# ProProject_HV_No_Display_2024-06-09.net
KiCad netlist of a schematic drawn in EasyEDA Pro
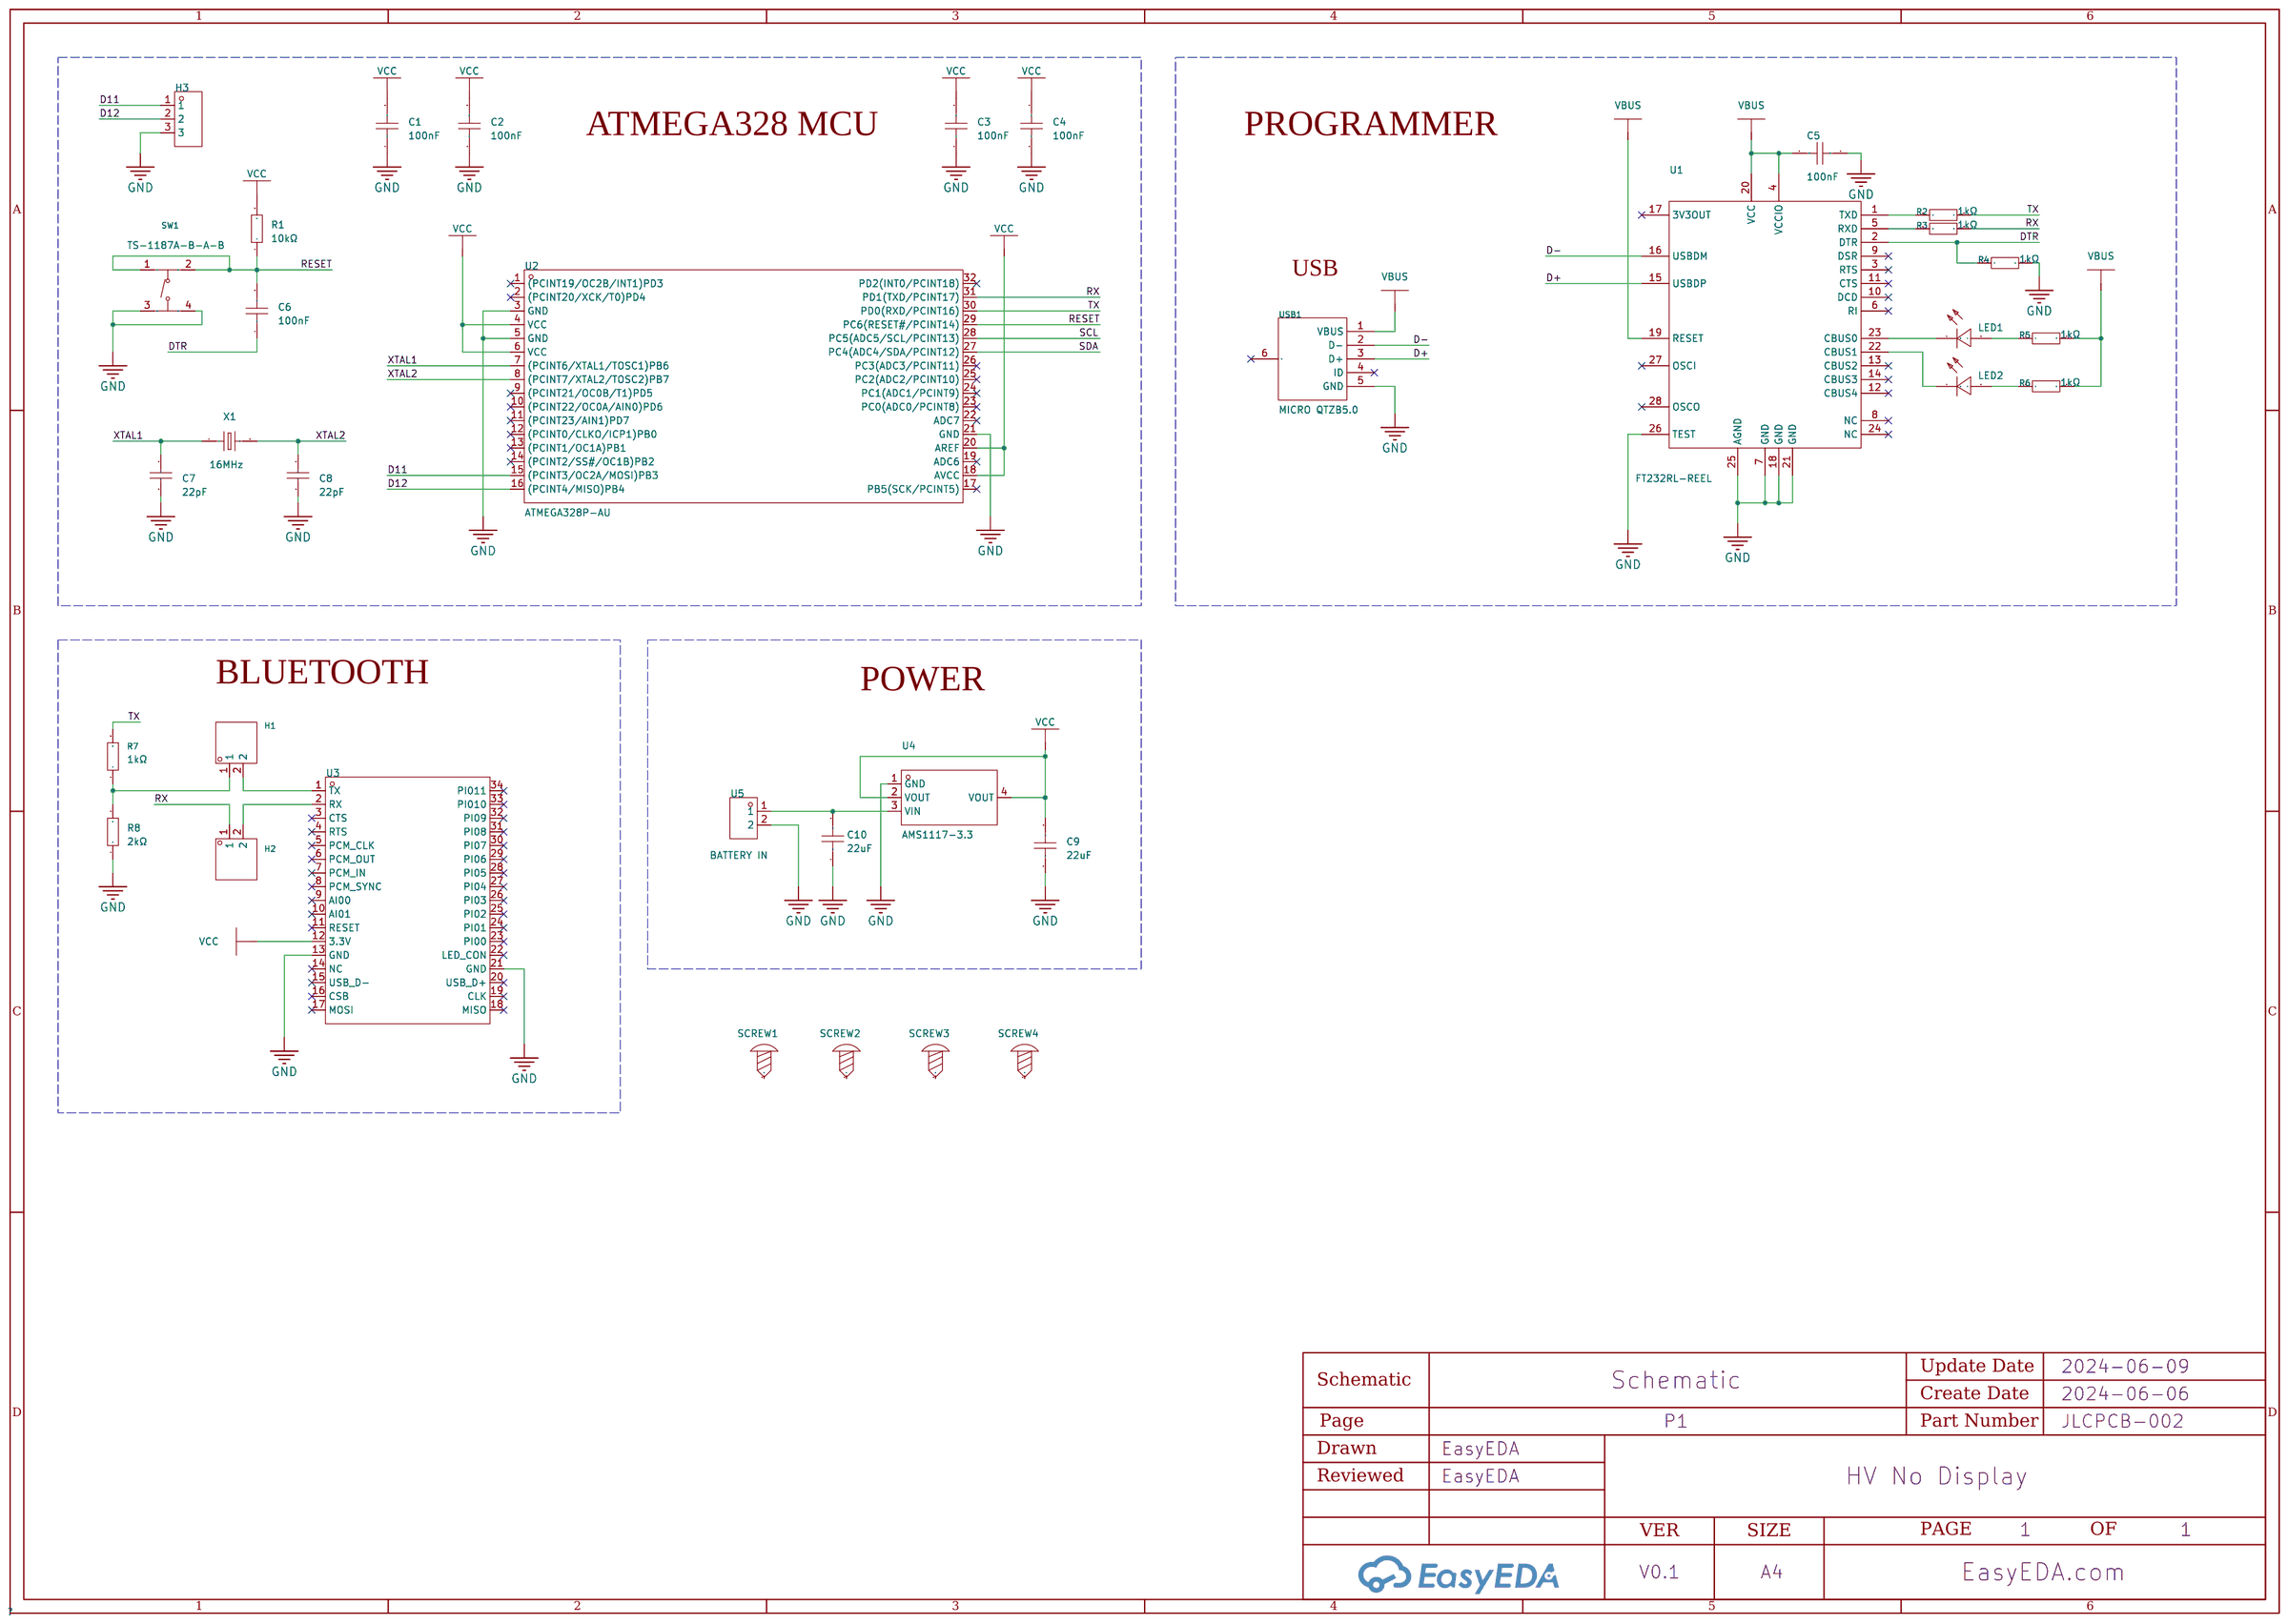
[diagram p0: schematic sheet]

(export (version "E")
  (design (tool "Eeschema 10.0.6"))
  (components
    (comp (ref "C1")
      (value "100nF")
      (footprint "easyedapro:C0402")
      (fields
        (field (name "Manufacturer Part") "CL05B104KB54PNC")
        (field (name "Manufacturer") "SAMSUNG(三星)")
      )
      (libsource (lib "easyedapro") (part "CL05B104KB54PNC"))
    )
    (comp (ref "C2")
      (value "100nF")
      (footprint "easyedapro:C0402")
      (fields
        (field (name "Manufacturer Part") "CL05B104KB54PNC")
        (field (name "Manufacturer") "SAMSUNG(三星)")
      )
      (libsource (lib "easyedapro") (part "CL05B104KB54PNC"))
    )
    (comp (ref "C3")
      (value "100nF")
      (footprint "easyedapro:C0402")
      (fields
        (field (name "Manufacturer Part") "CL05B104KB54PNC")
        (field (name "Manufacturer") "SAMSUNG(三星)")
      )
      (libsource (lib "easyedapro") (part "CL05B104KB54PNC"))
    )
    (comp (ref "C4")
      (value "100nF")
      (footprint "easyedapro:C0402")
      (fields
        (field (name "Manufacturer Part") "CL05B104KB54PNC")
        (field (name "Manufacturer") "SAMSUNG(三星)")
      )
      (libsource (lib "easyedapro") (part "CL05B104KB54PNC"))
    )
    (comp (ref "C5")
      (value "100nF")
      (footprint "easyedapro:C0402")
      (fields
        (field (name "Manufacturer Part") "CL05B104KB54PNC")
        (field (name "Manufacturer") "SAMSUNG(三星)")
      )
      (libsource (lib "easyedapro") (part "CL05B104KB54PNC"))
    )
    (comp (ref "C6")
      (value "100nF")
      (footprint "easyedapro:C0402")
      (fields
        (field (name "Manufacturer Part") "CL05B104KB54PNC")
        (field (name "Manufacturer") "SAMSUNG(三星)")
      )
      (libsource (lib "easyedapro") (part "CL05B104KB54PNC"))
    )
    (comp (ref "C7")
      (value "22pF")
      (footprint "easyedapro:C0402")
      (fields (field (name "Manufacturer Part") "0402CG220J500NT") (field (name "Manufacturer") "FH(风华)"))
      (libsource (lib "easyedapro") (part "0402CG220J500NT"))
    )
    (comp (ref "C8")
      (value "22pF")
      (footprint "easyedapro:C0402")
      (fields (field (name "Manufacturer Part") "0402CG220J500NT") (field (name "Manufacturer") "FH(风华)"))
      (libsource (lib "easyedapro") (part "0402CG220J500NT"))
    )
    (comp (ref "C9")
      (value "22uF")
      (footprint "easyedapro:C0805")
      (fields
        (field (name "Manufacturer Part") "CL21A226MAQNNNE")
        (field (name "Manufacturer") "SAMSUNG(三星)")
      )
      (libsource (lib "easyedapro") (part "CL21A226MAQNNNE"))
    )
    (comp (ref "C10")
      (value "22uF")
      (footprint "easyedapro:C0805")
      (fields
        (field (name "Manufacturer Part") "CL21A226MAQNNNE")
        (field (name "Manufacturer") "SAMSUNG(三星)")
      )
      (libsource (lib "easyedapro") (part "CL21A226MAQNNNE"))
    )
    (comp (ref "H1")
      (value "~")
      (footprint "easyedapro:HDR-TH_2P-P2.54-V-M-1")
      (libsource (lib "easyedapro") (part "210S-1*2P L=11.6MMGold-plated black"))
    )
    (comp (ref "H2")
      (value "~")
      (footprint "easyedapro:HDR-TH_2P-P2.54-V-M-1")
      (libsource (lib "easyedapro") (part "210S-1*2P L=11.6MMGold-plated black"))
    )
    (comp (ref "H3")
      (value "~")
      (footprint "easyedapro:HDR-TH_3P-P2.54-V-M")
      (libsource (lib "easyedapro") (part "PZ254V-11-03P_C2937625"))
    )
    (comp (ref "LED1")
      (value "TJ-S1005SW4TGLC2R-A5")
      (footprint "easyedapro:LED0402-RD")
      (description "Emitted Color:Red")
      (fields (field (name "Manufacturer") "TOGIALED(统佳)"))
      (libsource (lib "easyedapro") (part "TJ-S1005SW4TGLC2R-A5"))
    )
    (comp (ref "LED2")
      (value "TJ-S1005SW4TGLC2R-A5")
      (footprint "easyedapro:LED0402-RD")
      (description "Emitted Color:Red")
      (fields (field (name "Manufacturer") "TOGIALED(统佳)"))
      (libsource (lib "easyedapro") (part "TJ-S1005SW4TGLC2R-A5"))
    )
    (comp (ref "R1")
      (value "10kΩ")
      (footprint "easyedapro:R0402")
      (fields
        (field (name "Manufacturer Part") "0402WGF1002TCE")
        (field (name "Manufacturer") "UNI-ROYAL(厚声)")
      )
      (libsource (lib "easyedapro") (part "0402WGF1002TCE"))
    )
    (comp (ref "R2")
      (value "1kΩ")
      (footprint "easyedapro:R0402")
      (fields
        (field (name "Manufacturer Part") "0402WGF1001TCE")
        (field (name "Manufacturer") "UNI-ROYAL(厚声)")
      )
      (libsource (lib "easyedapro") (part "0402WGF1001TCE"))
    )
    (comp (ref "R3")
      (value "1kΩ")
      (footprint "easyedapro:R0402")
      (fields
        (field (name "Manufacturer Part") "0402WGF1001TCE")
        (field (name "Manufacturer") "UNI-ROYAL(厚声)")
      )
      (libsource (lib "easyedapro") (part "0402WGF1001TCE"))
    )
    (comp (ref "R4")
      (value "1kΩ")
      (footprint "easyedapro:R0402")
      (fields
        (field (name "Manufacturer Part") "0402WGF1001TCE")
        (field (name "Manufacturer") "UNI-ROYAL(厚声)")
      )
      (libsource (lib "easyedapro") (part "0402WGF1001TCE"))
    )
    (comp (ref "R5")
      (value "1kΩ")
      (footprint "easyedapro:R0402")
      (fields
        (field (name "Manufacturer Part") "0402WGF1001TCE")
        (field (name "Manufacturer") "UNI-ROYAL(厚声)")
      )
      (libsource (lib "easyedapro") (part "0402WGF1001TCE"))
    )
    (comp (ref "R6")
      (value "1kΩ")
      (footprint "easyedapro:R0402")
      (fields
        (field (name "Manufacturer Part") "0402WGF1001TCE")
        (field (name "Manufacturer") "UNI-ROYAL(厚声)")
      )
      (libsource (lib "easyedapro") (part "0402WGF1001TCE"))
    )
    (comp (ref "R7")
      (value "1kΩ")
      (footprint "easyedapro:R0402")
      (fields
        (field (name "Manufacturer Part") "0402WGF1001TCE")
        (field (name "Manufacturer") "UNI-ROYAL(厚声)")
      )
      (libsource (lib "easyedapro") (part "0402WGF1001TCE"))
    )
    (comp (ref "R8")
      (value "2kΩ")
      (footprint "easyedapro:R0402")
      (fields
        (field (name "Manufacturer Part") "0402WGF2001TCE")
        (field (name "Manufacturer") "UNI-ROYAL(厚声)")
      )
      (libsource (lib "easyedapro") (part "0402WGF2001TCE"))
    )
    (comp (ref "SCREW1")
      (value "~")
      (footprint "easyedapro:Screw-Hole-M2")
      (libsource (lib "easyedapro") (part "Screw-Hole"))
    )
    (comp (ref "SCREW2")
      (value "~")
      (footprint "easyedapro:Screw-Hole-M2")
      (libsource (lib "easyedapro") (part "Screw-Hole"))
    )
    (comp (ref "SCREW3")
      (value "~")
      (footprint "easyedapro:Screw-Hole-M2")
      (libsource (lib "easyedapro") (part "Screw-Hole"))
    )
    (comp (ref "SCREW4")
      (value "~")
      (footprint "easyedapro:Screw-Hole-M2")
      (libsource (lib "easyedapro") (part "Screw-Hole"))
    )
    (comp (ref "SW1")
      (value "TS-1187A-B-A-B")
      (footprint "easyedapro:SW-SMD_4P-L5.1-W5.1-P3.70-LS6.5-TL-2")
      (fields (field (name "Manufacturer") "XKB Connectivity(中国星坤)"))
      (libsource (lib "easyedapro") (part "TS-1187A-B-A-B"))
    )
    (comp (ref "U1")
      (value "FT232RL-REEL")
      (footprint "easyedapro:SSOP-28_L10.2-W5.3-P0.65-LS7.8-BL")
      (fields (field (name "Manufacturer") "FTDI(飞特帝亚)"))
      (libsource (lib "easyedapro") (part "FT232RL-REEL"))
    )
    (comp (ref "U2")
      (value "ATMEGA328P-AU")
      (footprint "easyedapro:TQFP-32_L7.0-W7.0-P0.80-LS9.0-BL")
      (fields (field (name "Manufacturer") "MICROCHIP(美国微芯)"))
      (libsource (lib "easyedapro") (part "ATMEGA328P-AU"))
    )
    (comp (ref "U3")
      (value "{ManufacturerPart!}")
      (footprint "easyedapro:BULETM-SMD_HC-05")
      (fields (field (name "Manufacturer Part") "HC-05"))
      (libsource (lib "easyedapro") (part "HC-05"))
    )
    (comp (ref "U4")
      (value "AMS1117-3.3")
      (footprint "easyedapro:SOT-223-3_L6.5-W3.4-P2.30-LS7.0-BR")
      (fields (field (name "Manufacturer") "AMS"))
      (libsource (lib "easyedapro") (part "AMS1117-3.3"))
    )
    (comp (ref "U5")
      (value "BATTERY IN")
      (footprint "easyedapro:CONN-TH_2P-P5.08_DB128L-5.08-2P")
      (fields (field (name "Manufacturer") "DORABO(地博电气)"))
      (libsource (lib "easyedapro") (part "DB128L-5.08-2P"))
    )
    (comp (ref "USB1")
      (value "MICRO QTZB5.0")
      (footprint "easyedapro:MICRO-USB-SMD_MICRO-QTZB5.0")
      (fields (field (name "Manufacturer") "SHOU HAN(首韩)"))
      (libsource (lib "easyedapro") (part "MICRO QTZB5.0"))
    )
    (comp (ref "X1")
      (value "16MHz")
      (footprint "easyedapro:HC-49S_L11.4-W4.8")
      (fields (field (name "Manufacturer Part") "TAXM16M2GLFBET2T") (field (name "Manufacturer") "YJX(雅晶鑫)"))
      (libsource (lib "easyedapro") (part "HC-49SM16MHz20pF30ppm"))
    )
  )
  (nets
    (net (code "1") (name "/D+") (class "Default")
      (node (ref "U1") (pin "15") (pinfunction "USBDP_15") (pintype "bidirectional"))
      (node (ref "USB1") (pin "3") (pinfunction "D+_3") (pintype "input"))
    )
    (net (code "2") (name "/D-") (class "Default")
      (node (ref "U1") (pin "16") (pinfunction "USBDM_16") (pintype "bidirectional"))
      (node (ref "USB1") (pin "2") (pinfunction "D-_2") (pintype "input"))
    )
    (net (code "3") (name "/D11") (class "Default")
      (node (ref "H3") (pin "1") (pinfunction "1_1") (pintype "input"))
      (node (ref "U2") (pin "15") (pinfunction "(PCINT3/OC2A/MOSI)PB3_15") (pintype "unspecified"))
    )
    (net (code "4") (name "/D12") (class "Default")
      (node (ref "H3") (pin "2") (pinfunction "2_2") (pintype "input"))
      (node (ref "U2") (pin "16") (pinfunction "(PCINT4/MISO)PB4_16") (pintype "unspecified"))
    )
    (net (code "5") (name "/DTR") (class "Default")
      (node (ref "C6") (pin "1") (pinfunction "1_1") (pintype "input"))
      (node (ref "R4") (pin "1") (pinfunction "1_1") (pintype "input"))
      (node (ref "U1") (pin "2") (pinfunction "DTR_2") (pintype "output"))
    )
    (net (code "6") (name "/RESET") (class "Default")
      (node (ref "C6") (pin "2") (pinfunction "2_2") (pintype "input"))
      (node (ref "R1") (pin "1") (pinfunction "1_1") (pintype "input"))
      (node (ref "SW1") (pin "1") (pinfunction "A_1") (pintype "input"))
      (node (ref "SW1") (pin "2") (pinfunction "B_2") (pintype "input"))
      (node (ref "U2") (pin "29") (pinfunction "PC6(RESET#/PCINT14)_29") (pintype "unspecified"))
    )
    (net (code "7") (name "/RX") (class "Default")
      (node (ref "H2") (pin "1") (pinfunction "1_1") (pintype "input"))
      (node (ref "R3") (pin "2") (pinfunction "2_2") (pintype "input"))
      (node (ref "U2") (pin "31") (pinfunction "PD1(TXD/PCINT17)_31") (pintype "unspecified"))
    )
    (net (code "8") (name "/SCL") (class "Default")
      (node (ref "U2") (pin "28") (pinfunction "PC5(ADC5/SCL/PCINT13)_28") (pintype "unspecified"))
    )
    (net (code "9") (name "/SDA") (class "Default")
      (node (ref "U2") (pin "27") (pinfunction "PC4(ADC4/SDA/PCINT12)_27") (pintype "unspecified"))
    )
    (net (code "10") (name "/TX") (class "Default")
      (node (ref "R2") (pin "2") (pinfunction "2_2") (pintype "input"))
      (node (ref "R7") (pin "2") (pinfunction "2_2") (pintype "input"))
      (node (ref "U2") (pin "30") (pinfunction "PD0(RXD/PCINT16)_30") (pintype "unspecified"))
    )
    (net (code "11") (name "/XTAL1") (class "Default")
      (node (ref "C7") (pin "2") (pinfunction "2_2") (pintype "input"))
      (node (ref "U2") (pin "7") (pinfunction "(PCINT6/XTAL1/TOSC1)PB6_7") (pintype "unspecified"))
      (node (ref "X1") (pin "1") (pinfunction "1_1") (pintype "unspecified"))
    )
    (net (code "12") (name "/XTAL2") (class "Default")
      (node (ref "C8") (pin "2") (pinfunction "2_2") (pintype "input"))
      (node (ref "U2") (pin "8") (pinfunction "(PCINT7/XTAL2/TOSC2)PB7_8") (pintype "unspecified"))
      (node (ref "X1") (pin "2") (pinfunction "2_2") (pintype "unspecified"))
    )
    (net (code "13") (name "GND") (class "Default")
      (node (ref "C1") (pin "1") (pinfunction "1_1") (pintype "input"))
      (node (ref "C10") (pin "1") (pinfunction "1_1") (pintype "unspecified"))
      (node (ref "C2") (pin "1") (pinfunction "1_1") (pintype "input"))
      (node (ref "C3") (pin "1") (pinfunction "1_1") (pintype "input"))
      (node (ref "C4") (pin "1") (pinfunction "1_1") (pintype "input"))
      (node (ref "C5") (pin "1") (pinfunction "1_1") (pintype "input"))
      (node (ref "C7") (pin "1") (pinfunction "1_1") (pintype "input"))
      (node (ref "C8") (pin "1") (pinfunction "1_1") (pintype "input"))
      (node (ref "C9") (pin "1") (pinfunction "1_1") (pintype "unspecified"))
      (node (ref "H3") (pin "3") (pinfunction "3_3") (pintype "input"))
      (node (ref "R4") (pin "2") (pinfunction "2_2") (pintype "input"))
      (node (ref "R8") (pin "1") (pinfunction "1_1") (pintype "input"))
      (node (ref "SW1") (pin "3") (pinfunction "C_3") (pintype "input"))
      (node (ref "SW1") (pin "4") (pinfunction "D_4") (pintype "input"))
      (node (ref "U1") (pin "18") (pinfunction "GND_18") (pintype "unspecified"))
      (node (ref "U1") (pin "21") (pinfunction "GND_21") (pintype "unspecified"))
      (node (ref "U1") (pin "25") (pinfunction "AGND_25") (pintype "unspecified"))
      (node (ref "U1") (pin "26") (pinfunction "TEST_26") (pintype "unspecified"))
      (node (ref "U1") (pin "7") (pinfunction "GND_7") (pintype "unspecified"))
      (node (ref "U2") (pin "21") (pinfunction "GND_21") (pintype "unspecified"))
      (node (ref "U2") (pin "3") (pinfunction "GND_3") (pintype "unspecified"))
      (node (ref "U2") (pin "5") (pinfunction "GND_5") (pintype "unspecified"))
      (node (ref "U3") (pin "13") (pinfunction "GND_13") (pintype "input"))
      (node (ref "U3") (pin "21") (pinfunction "GND_21") (pintype "input"))
      (node (ref "U4") (pin "1") (pinfunction "GND_1") (pintype "unspecified"))
      (node (ref "U5") (pin "2") (pinfunction "2_2") (pintype "unspecified"))
      (node (ref "USB1") (pin "5") (pinfunction "GND_5") (pintype "input"))
    )
    (net (code "14") (name "Net-(H1-Pad1)") (class "Default")
      (node (ref "H1") (pin "1") (pinfunction "1_1") (pintype "input"))
      (node (ref "R7") (pin "1") (pinfunction "1_1") (pintype "input"))
      (node (ref "R8") (pin "2") (pinfunction "2_2") (pintype "input"))
    )
    (net (code "15") (name "Net-(LED1-A)") (class "Default")
      (node (ref "LED1") (pin "2") (pinfunction "A_2") (pintype "unspecified"))
      (node (ref "R5") (pin "1") (pinfunction "1_1") (pintype "input"))
    )
    (net (code "16") (name "Net-(LED1-C)") (class "Default")
      (node (ref "LED1") (pin "1") (pinfunction "C_1") (pintype "unspecified"))
      (node (ref "U1") (pin "23") (pinfunction "CBUS0_23") (pintype "bidirectional"))
    )
    (net (code "17") (name "Net-(LED2-A)") (class "Default")
      (node (ref "LED2") (pin "2") (pinfunction "A_2") (pintype "unspecified"))
      (node (ref "R6") (pin "1") (pinfunction "1_1") (pintype "input"))
    )
    (net (code "18") (name "Net-(LED2-C)") (class "Default")
      (node (ref "LED2") (pin "1") (pinfunction "C_1") (pintype "unspecified"))
      (node (ref "U1") (pin "22") (pinfunction "CBUS1_22") (pintype "bidirectional"))
    )
    (net (code "19") (name "Net-(U1-RXD)") (class "Default")
      (node (ref "R3") (pin "1") (pinfunction "1_1") (pintype "input"))
      (node (ref "U1") (pin "5") (pinfunction "RXD_5") (pintype "unspecified"))
    )
    (net (code "20") (name "Net-(U1-TXD)") (class "Default")
      (node (ref "R2") (pin "1") (pinfunction "1_1") (pintype "input"))
      (node (ref "U1") (pin "1") (pinfunction "TXD_1") (pintype "output"))
    )
    (net (code "21") (name "Net-(U3-RX)") (class "Default")
      (node (ref "H2") (pin "2") (pinfunction "2_2") (pintype "input"))
      (node (ref "U3") (pin "2") (pinfunction "RX_2") (pintype "input"))
    )
    (net (code "22") (name "Net-(U3-TX)") (class "Default")
      (node (ref "H1") (pin "2") (pinfunction "2_2") (pintype "input"))
      (node (ref "U3") (pin "1") (pinfunction "TX_1") (pintype "input"))
    )
    (net (code "23") (name "Net-(U4-VIN)") (class "Default")
      (node (ref "C10") (pin "2") (pinfunction "2_2") (pintype "unspecified"))
      (node (ref "U4") (pin "3") (pinfunction "VIN_3") (pintype "unspecified"))
      (node (ref "U5") (pin "1") (pinfunction "1_1") (pintype "unspecified"))
    )
    (net (code "24") (name "VBUS") (class "Default")
      (node (ref "C5") (pin "2") (pinfunction "2_2") (pintype "input"))
      (node (ref "R5") (pin "2") (pinfunction "2_2") (pintype "input"))
      (node (ref "R6") (pin "2") (pinfunction "2_2") (pintype "input"))
      (node (ref "U1") (pin "19") (pinfunction "RESET_19") (pintype "unspecified"))
      (node (ref "U1") (pin "20") (pinfunction "VCC_20") (pintype "unspecified"))
      (node (ref "U1") (pin "4") (pinfunction "VCCIO_4") (pintype "unspecified"))
      (node (ref "USB1") (pin "1") (pinfunction "VBUS_1") (pintype "input"))
    )
    (net (code "25") (name "VCC") (class "Default")
      (node (ref "C1") (pin "2") (pinfunction "2_2") (pintype "input"))
      (node (ref "C2") (pin "2") (pinfunction "2_2") (pintype "input"))
      (node (ref "C3") (pin "2") (pinfunction "2_2") (pintype "input"))
      (node (ref "C4") (pin "2") (pinfunction "2_2") (pintype "input"))
      (node (ref "C9") (pin "2") (pinfunction "2_2") (pintype "unspecified"))
      (node (ref "R1") (pin "2") (pinfunction "2_2") (pintype "input"))
      (node (ref "U2") (pin "18") (pinfunction "AVCC_18") (pintype "unspecified"))
      (node (ref "U2") (pin "20") (pinfunction "AREF_20") (pintype "unspecified"))
      (node (ref "U2") (pin "4") (pinfunction "VCC_4") (pintype "unspecified"))
      (node (ref "U2") (pin "6") (pinfunction "VCC_6") (pintype "unspecified"))
      (node (ref "U3") (pin "12") (pinfunction "3.3V_12") (pintype "input"))
      (node (ref "U4") (pin "2") (pinfunction "VOUT_2") (pintype "unspecified"))
      (node (ref "U4") (pin "4") (pinfunction "VOUT_4") (pintype "unspecified"))
    )
    (net (code "26") (name "unconnected-(SCREW1-Pad1)") (class "Default")
      (node (ref "SCREW1") (pin "1") (pinfunction "1_1") (pintype "input"))
    )
    (net (code "27") (name "unconnected-(SCREW2-Pad1)") (class "Default")
      (node (ref "SCREW2") (pin "1") (pinfunction "1_1") (pintype "input"))
    )
    (net (code "28") (name "unconnected-(SCREW3-Pad1)") (class "Default")
      (node (ref "SCREW3") (pin "1") (pinfunction "1_1") (pintype "input"))
    )
    (net (code "29") (name "unconnected-(SCREW4-Pad1)") (class "Default")
      (node (ref "SCREW4") (pin "1") (pinfunction "1_1") (pintype "input"))
    )
    (net (code "30") (name "unconnected-(U1-3V3OUT-Pad17)") (class "Default")
      (node (ref "U1") (pin "17") (pinfunction "3V3OUT_17") (pintype "output+no_connect"))
    )
    (net (code "31") (name "unconnected-(U1-CBUS2-Pad13)") (class "Default")
      (node (ref "U1") (pin "13") (pinfunction "CBUS2_13") (pintype "bidirectional+no_connect"))
    )
    (net (code "32") (name "unconnected-(U1-CBUS3-Pad14)") (class "Default")
      (node (ref "U1") (pin "14") (pinfunction "CBUS3_14") (pintype "bidirectional+no_connect"))
    )
    (net (code "33") (name "unconnected-(U1-CBUS4-Pad12)") (class "Default")
      (node (ref "U1") (pin "12") (pinfunction "CBUS4_12") (pintype "bidirectional+no_connect"))
    )
    (net (code "34") (name "unconnected-(U1-CTS-Pad11)") (class "Default")
      (node (ref "U1") (pin "11") (pinfunction "CTS_11") (pintype "unspecified+no_connect"))
    )
    (net (code "35") (name "unconnected-(U1-DCD-Pad10)") (class "Default")
      (node (ref "U1") (pin "10") (pinfunction "DCD_10") (pintype "unspecified+no_connect"))
    )
    (net (code "36") (name "unconnected-(U1-DSR-Pad9)") (class "Default")
      (node (ref "U1") (pin "9") (pinfunction "DSR_9") (pintype "unspecified+no_connect"))
    )
    (net (code "37") (name "unconnected-(U1-NC-Pad8)") (class "Default")
      (node (ref "U1") (pin "8") (pinfunction "NC_8") (pintype "unspecified+no_connect"))
    )
    (net (code "38") (name "unconnected-(U1-NC-Pad24)") (class "Default")
      (node (ref "U1") (pin "24") (pinfunction "NC_24") (pintype "unspecified+no_connect"))
    )
    (net (code "39") (name "unconnected-(U1-OSCI-Pad27)") (class "Default")
      (node (ref "U1") (pin "27") (pinfunction "OSCI_27") (pintype "unspecified+no_connect"))
    )
    (net (code "40") (name "unconnected-(U1-OSCO-Pad28)") (class "Default")
      (node (ref "U1") (pin "28") (pinfunction "OSCO_28") (pintype "output+no_connect"))
    )
    (net (code "41") (name "unconnected-(U1-RI-Pad6)") (class "Default")
      (node (ref "U1") (pin "6") (pinfunction "RI_6") (pintype "unspecified+no_connect"))
    )
    (net (code "42") (name "unconnected-(U1-RTS-Pad3)") (class "Default")
      (node (ref "U1") (pin "3") (pinfunction "RTS_3") (pintype "output+no_connect"))
    )
    (net (code "43") (name "unconnected-(U2-(PCINT0{slash}CLKO{slash}ICP1)PB0-Pad12)") (class "Default")
      (node (ref "U2") (pin "12") (pinfunction "(PCINT0/CLKO/ICP1)PB0_12") (pintype "unspecified+no_connect"))
    )
    (net (code "44") (name "unconnected-(U2-(PCINT1{slash}OC1A)PB1-Pad13)") (class "Default")
      (node (ref "U2") (pin "13") (pinfunction "(PCINT1/OC1A)PB1_13") (pintype "unspecified+no_connect"))
    )
    (net (code "45") (name "unconnected-(U2-(PCINT2{slash}SS#{slash}OC1B)PB2-Pad14)") (class "Default")
      (node (ref "U2") (pin "14") (pinfunction "(PCINT2/SS#/OC1B)PB2_14") (pintype "unspecified+no_connect"))
    )
    (net (code "46") (name "unconnected-(U2-(PCINT19{slash}OC2B{slash}INT1)PD3-Pad1)") (class "Default")
      (node (ref "U2") (pin "1") (pinfunction "(PCINT19/OC2B/INT1)PD3_1") (pintype "unspecified+no_connect"))
    )
    (net (code "47") (name "unconnected-(U2-(PCINT20{slash}XCK{slash}T0)PD4-Pad2)") (class "Default")
      (node (ref "U2") (pin "2") (pinfunction "(PCINT20/XCK/T0)PD4_2") (pintype "unspecified+no_connect"))
    )
    (net (code "48") (name "unconnected-(U2-(PCINT21{slash}OC0B{slash}T1)PD5-Pad9)") (class "Default")
      (node (ref "U2") (pin "9") (pinfunction "(PCINT21/OC0B/T1)PD5_9") (pintype "unspecified+no_connect"))
    )
    (net (code "49") (name "unconnected-(U2-(PCINT22{slash}OC0A{slash}AIN0)PD6-Pad10)") (class "Default")
      (node (ref "U2") (pin "10") (pinfunction "(PCINT22/OC0A/AIN0)PD6_10") (pintype "unspecified+no_connect"))
    )
    (net (code "50") (name "unconnected-(U2-(PCINT23{slash}AIN1)PD7-Pad11)") (class "Default")
      (node (ref "U2") (pin "11") (pinfunction "(PCINT23/AIN1)PD7_11") (pintype "unspecified+no_connect"))
    )
    (net (code "51") (name "unconnected-(U2-ADC6-Pad19)") (class "Default")
      (node (ref "U2") (pin "19") (pinfunction "ADC6_19") (pintype "unspecified+no_connect"))
    )
    (net (code "52") (name "unconnected-(U2-ADC7-Pad22)") (class "Default")
      (node (ref "U2") (pin "22") (pinfunction "ADC7_22") (pintype "unspecified+no_connect"))
    )
    (net (code "53") (name "unconnected-(U2-PB5(SCK{slash}PCINT5)-Pad17)") (class "Default")
      (node (ref "U2") (pin "17") (pinfunction "PB5(SCK/PCINT5)_17") (pintype "unspecified+no_connect"))
    )
    (net (code "54") (name "unconnected-(U2-PC0(ADC0{slash}PCINT8)-Pad23)") (class "Default")
      (node (ref "U2") (pin "23") (pinfunction "PC0(ADC0/PCINT8)_23") (pintype "unspecified+no_connect"))
    )
    (net (code "55") (name "unconnected-(U2-PC1(ADC1{slash}PCINT9)-Pad24)") (class "Default")
      (node (ref "U2") (pin "24") (pinfunction "PC1(ADC1/PCINT9)_24") (pintype "unspecified+no_connect"))
    )
    (net (code "56") (name "unconnected-(U2-PC2(ADC2{slash}PCINT10)-Pad25)") (class "Default")
      (node (ref "U2") (pin "25") (pinfunction "PC2(ADC2/PCINT10)_25") (pintype "unspecified+no_connect"))
    )
    (net (code "57") (name "unconnected-(U2-PC3(ADC3{slash}PCINT11)-Pad26)") (class "Default")
      (node (ref "U2") (pin "26") (pinfunction "PC3(ADC3/PCINT11)_26") (pintype "unspecified+no_connect"))
    )
    (net (code "58") (name "unconnected-(U2-PD2(INT0{slash}PCINT18)-Pad32)") (class "Default")
      (node (ref "U2") (pin "32") (pinfunction "PD2(INT0/PCINT18)_32") (pintype "unspecified+no_connect"))
    )
    (net (code "59") (name "unconnected-(U3-AI00-Pad9)") (class "Default")
      (node (ref "U3") (pin "9") (pinfunction "AI00_9") (pintype "input+no_connect"))
    )
    (net (code "60") (name "unconnected-(U3-AI01-Pad10)") (class "Default")
      (node (ref "U3") (pin "10") (pinfunction "AI01_10") (pintype "input+no_connect"))
    )
    (net (code "61") (name "unconnected-(U3-CLK-Pad19)") (class "Default")
      (node (ref "U3") (pin "19") (pinfunction "CLK_19") (pintype "input+no_connect"))
    )
    (net (code "62") (name "unconnected-(U3-CSB-Pad16)") (class "Default")
      (node (ref "U3") (pin "16") (pinfunction "CSB_16") (pintype "input+no_connect"))
    )
    (net (code "63") (name "unconnected-(U3-CTS-Pad3)") (class "Default")
      (node (ref "U3") (pin "3") (pinfunction "CTS_3") (pintype "input+no_connect"))
    )
    (net (code "64") (name "unconnected-(U3-LED_CON-Pad22)") (class "Default")
      (node (ref "U3") (pin "22") (pinfunction "LED_CON_22") (pintype "input+no_connect"))
    )
    (net (code "65") (name "unconnected-(U3-MISO-Pad18)") (class "Default")
      (node (ref "U3") (pin "18") (pinfunction "MISO_18") (pintype "input+no_connect"))
    )
    (net (code "66") (name "unconnected-(U3-MOSI-Pad17)") (class "Default")
      (node (ref "U3") (pin "17") (pinfunction "MOSI_17") (pintype "input+no_connect"))
    )
    (net (code "67") (name "unconnected-(U3-NC-Pad14)") (class "Default")
      (node (ref "U3") (pin "14") (pinfunction "NC_14") (pintype "input+no_connect"))
    )
    (net (code "68") (name "unconnected-(U3-PCM_CLK-Pad5)") (class "Default")
      (node (ref "U3") (pin "5") (pinfunction "PCM_CLK_5") (pintype "input+no_connect"))
    )
    (net (code "69") (name "unconnected-(U3-PCM_IN-Pad7)") (class "Default")
      (node (ref "U3") (pin "7") (pinfunction "PCM_IN_7") (pintype "input+no_connect"))
    )
    (net (code "70") (name "unconnected-(U3-PCM_OUT-Pad6)") (class "Default")
      (node (ref "U3") (pin "6") (pinfunction "PCM_OUT_6") (pintype "input+no_connect"))
    )
    (net (code "71") (name "unconnected-(U3-PCM_SYNC-Pad8)") (class "Default")
      (node (ref "U3") (pin "8") (pinfunction "PCM_SYNC_8") (pintype "input+no_connect"))
    )
    (net (code "72") (name "unconnected-(U3-PI00-Pad23)") (class "Default")
      (node (ref "U3") (pin "23") (pinfunction "PI00_23") (pintype "input+no_connect"))
    )
    (net (code "73") (name "unconnected-(U3-PI01-Pad24)") (class "Default")
      (node (ref "U3") (pin "24") (pinfunction "PI01_24") (pintype "input+no_connect"))
    )
    (net (code "74") (name "unconnected-(U3-PI02-Pad25)") (class "Default")
      (node (ref "U3") (pin "25") (pinfunction "PI02_25") (pintype "input+no_connect"))
    )
    (net (code "75") (name "unconnected-(U3-PI03-Pad26)") (class "Default")
      (node (ref "U3") (pin "26") (pinfunction "PI03_26") (pintype "input+no_connect"))
    )
    (net (code "76") (name "unconnected-(U3-PI04-Pad27)") (class "Default")
      (node (ref "U3") (pin "27") (pinfunction "PI04_27") (pintype "input+no_connect"))
    )
    (net (code "77") (name "unconnected-(U3-PI05-Pad28)") (class "Default")
      (node (ref "U3") (pin "28") (pinfunction "PI05_28") (pintype "input+no_connect"))
    )
    (net (code "78") (name "unconnected-(U3-PI06-Pad29)") (class "Default")
      (node (ref "U3") (pin "29") (pinfunction "PI06_29") (pintype "input+no_connect"))
    )
    (net (code "79") (name "unconnected-(U3-PI07-Pad30)") (class "Default")
      (node (ref "U3") (pin "30") (pinfunction "PI07_30") (pintype "input+no_connect"))
    )
    (net (code "80") (name "unconnected-(U3-PI08-Pad31)") (class "Default")
      (node (ref "U3") (pin "31") (pinfunction "PI08_31") (pintype "input+no_connect"))
    )
    (net (code "81") (name "unconnected-(U3-PI09-Pad32)") (class "Default")
      (node (ref "U3") (pin "32") (pinfunction "PI09_32") (pintype "input+no_connect"))
    )
    (net (code "82") (name "unconnected-(U3-PI010-Pad33)") (class "Default")
      (node (ref "U3") (pin "33") (pinfunction "PI010_33") (pintype "input+no_connect"))
    )
    (net (code "83") (name "unconnected-(U3-PI011-Pad34)") (class "Default")
      (node (ref "U3") (pin "34") (pinfunction "PI011_34") (pintype "input+no_connect"))
    )
    (net (code "84") (name "unconnected-(U3-RESET-Pad11)") (class "Default")
      (node (ref "U3") (pin "11") (pinfunction "RESET_11") (pintype "input+no_connect"))
    )
    (net (code "85") (name "unconnected-(U3-RTS-Pad4)") (class "Default")
      (node (ref "U3") (pin "4") (pinfunction "RTS_4") (pintype "input+no_connect"))
    )
    (net (code "86") (name "unconnected-(U3-USB_D+-Pad20)") (class "Default")
      (node (ref "U3") (pin "20") (pinfunction "USB_D+_20") (pintype "input+no_connect"))
    )
    (net (code "87") (name "unconnected-(U3-USB_D--Pad15)") (class "Default")
      (node (ref "U3") (pin "15") (pinfunction "USB_D-_15") (pintype "input+no_connect"))
    )
    (net (code "88") (name "unconnected-(USB1-EH-Pad6)") (class "Default")
      (node (ref "USB1") (pin "6") (pinfunction "EH_6") (pintype "input+no_connect"))
    )
    (net (code "89") (name "unconnected-(USB1-ID-Pad4)") (class "Default")
      (node (ref "USB1") (pin "4") (pinfunction "ID_4") (pintype "input+no_connect"))
    )
  )
)
